# Fuente3_3VDC.net
KiCad netlist of a schematic drawn in Altium Designer
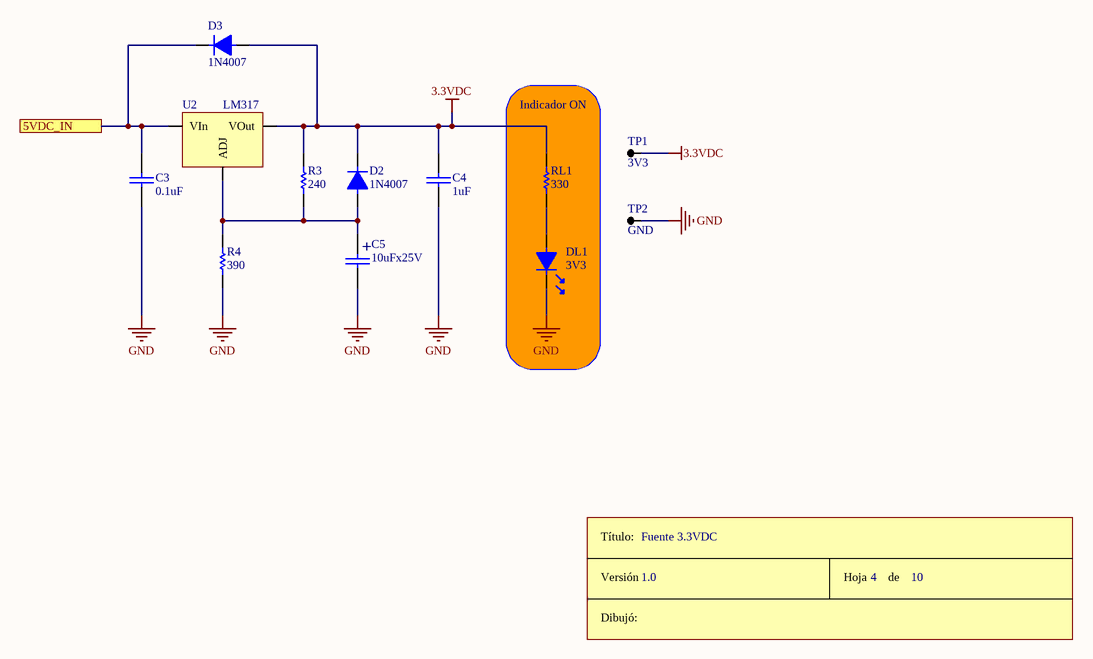
[diagram p0: Fuente3.3VDC.SchDoc]

(export (version "E")
  (design (tool "Eeschema 10.0.6"))
  (components
    (comp (ref "C3") (value "0.1uF") (footprint "CAP100") (libsource (lib "LIBEBAL") (part "CAP")))
    (comp (ref "C4") (value "1uF") (footprint "CAP100") (libsource (lib "LIBEBAL") (part "CAP")))
    (comp (ref "C5")
      (value "10uFx25V")
      (footprint "CAP100RP")
      (libsource (lib "AditionalComponents") (part "CAPPOL"))
    )
    (comp (ref "D2") (value "1N4007") (footprint "DO41") (libsource (lib "LIBEBAL") (part "DIODO")))
    (comp (ref "D3") (value "1N4007") (footprint "DO41") (libsource (lib "LIBEBAL") (part "DIODO")))
    (comp (ref "DL1") (value "3V3") (footprint "LED3") (libsource (lib "LIBEBAL") (part "LED")))
    (comp (ref "R3") (value "240") (footprint "RES300") (libsource (lib "LIBEBAL") (part "RES")))
    (comp (ref "R4") (value "390") (footprint "RES300") (libsource (lib "LIBEBAL") (part "RES")))
    (comp (ref "RL1") (value "330") (footprint "RES300") (libsource (lib "LIBEBAL") (part "RES")))
    (comp (ref "ROT2") (value "Rótulo") (libsource (lib "LIB PIO IX") (part "Rótulo")))
    (comp (ref "TP1")
      (value "3V3")
      (footprint "TPTH - PAD ONLY")
      (libsource (lib "AditionalComponents") (part "TP"))
    )
    (comp (ref "TP2")
      (value "GND")
      (footprint "TPTH - PAD ONLY")
      (libsource (lib "AditionalComponents") (part "TP"))
    )
    (comp (ref "U2")
      (value "LM317")
      (footprint "TO-220 V")
      (description "IC REG ADJ 1.5A 3 TERM TO-220")
      (libsource (lib "AditionalComponents") (part "LM317"))
    )
  )
  (nets
    (net (code "1") (name "/5VDC_IN") (class "Default")
      (node (ref "C3") (pin "1") (pinfunction "1_1") (pintype "passive"))
      (node (ref "D3") (pin "2") (pinfunction "2_2") (pintype "passive"))
      (node (ref "U2") (pin "3") (pinfunction "VIn_3") (pintype "passive"))
    )
    (net (code "2") (name "3.3VDC") (class "Default")
      (node (ref "C4") (pin "1") (pinfunction "1_1") (pintype "passive"))
      (node (ref "D2") (pin "2") (pinfunction "2_2") (pintype "passive"))
      (node (ref "D3") (pin "1") (pinfunction "1_1") (pintype "passive"))
      (node (ref "R3") (pin "2") (pinfunction "2_2") (pintype "passive"))
      (node (ref "RL1") (pin "2") (pinfunction "2_2") (pintype "passive"))
      (node (ref "TP1") (pin "1") (pinfunction "1_1") (pintype "passive"))
      (node (ref "U2") (pin "2") (pinfunction "VOut_2") (pintype "passive"))
    )
    (net (code "3") (name "GND") (class "Default")
      (node (ref "C3") (pin "2") (pinfunction "2_2") (pintype "passive"))
      (node (ref "C4") (pin "2") (pinfunction "2_2") (pintype "passive"))
      (node (ref "C5") (pin "2") (pinfunction "2_2") (pintype "passive"))
      (node (ref "DL1") (pin "2") (pinfunction "2_2") (pintype "passive"))
      (node (ref "R4") (pin "1") (pinfunction "1_1") (pintype "passive"))
      (node (ref "TP2") (pin "1") (pinfunction "1_1") (pintype "passive"))
    )
    (net (code "4") (name "Net-(DL1-Pad1)") (class "Default")
      (node (ref "DL1") (pin "1") (pinfunction "1_1") (pintype "passive"))
      (node (ref "RL1") (pin "1") (pinfunction "1_1") (pintype "passive"))
    )
    (net (code "5") (name "Net-(U2-ADJ)") (class "Default")
      (node (ref "C5") (pin "1") (pinfunction "1_1") (pintype "passive"))
      (node (ref "D2") (pin "1") (pinfunction "1_1") (pintype "passive"))
      (node (ref "R3") (pin "1") (pinfunction "1_1") (pintype "passive"))
      (node (ref "R4") (pin "2") (pinfunction "2_2") (pintype "passive"))
      (node (ref "U2") (pin "1") (pinfunction "ADJ_1") (pintype "passive"))
    )
  )
)
